# controller.net
KiCad netlist of a schematic drawn in EAGLE
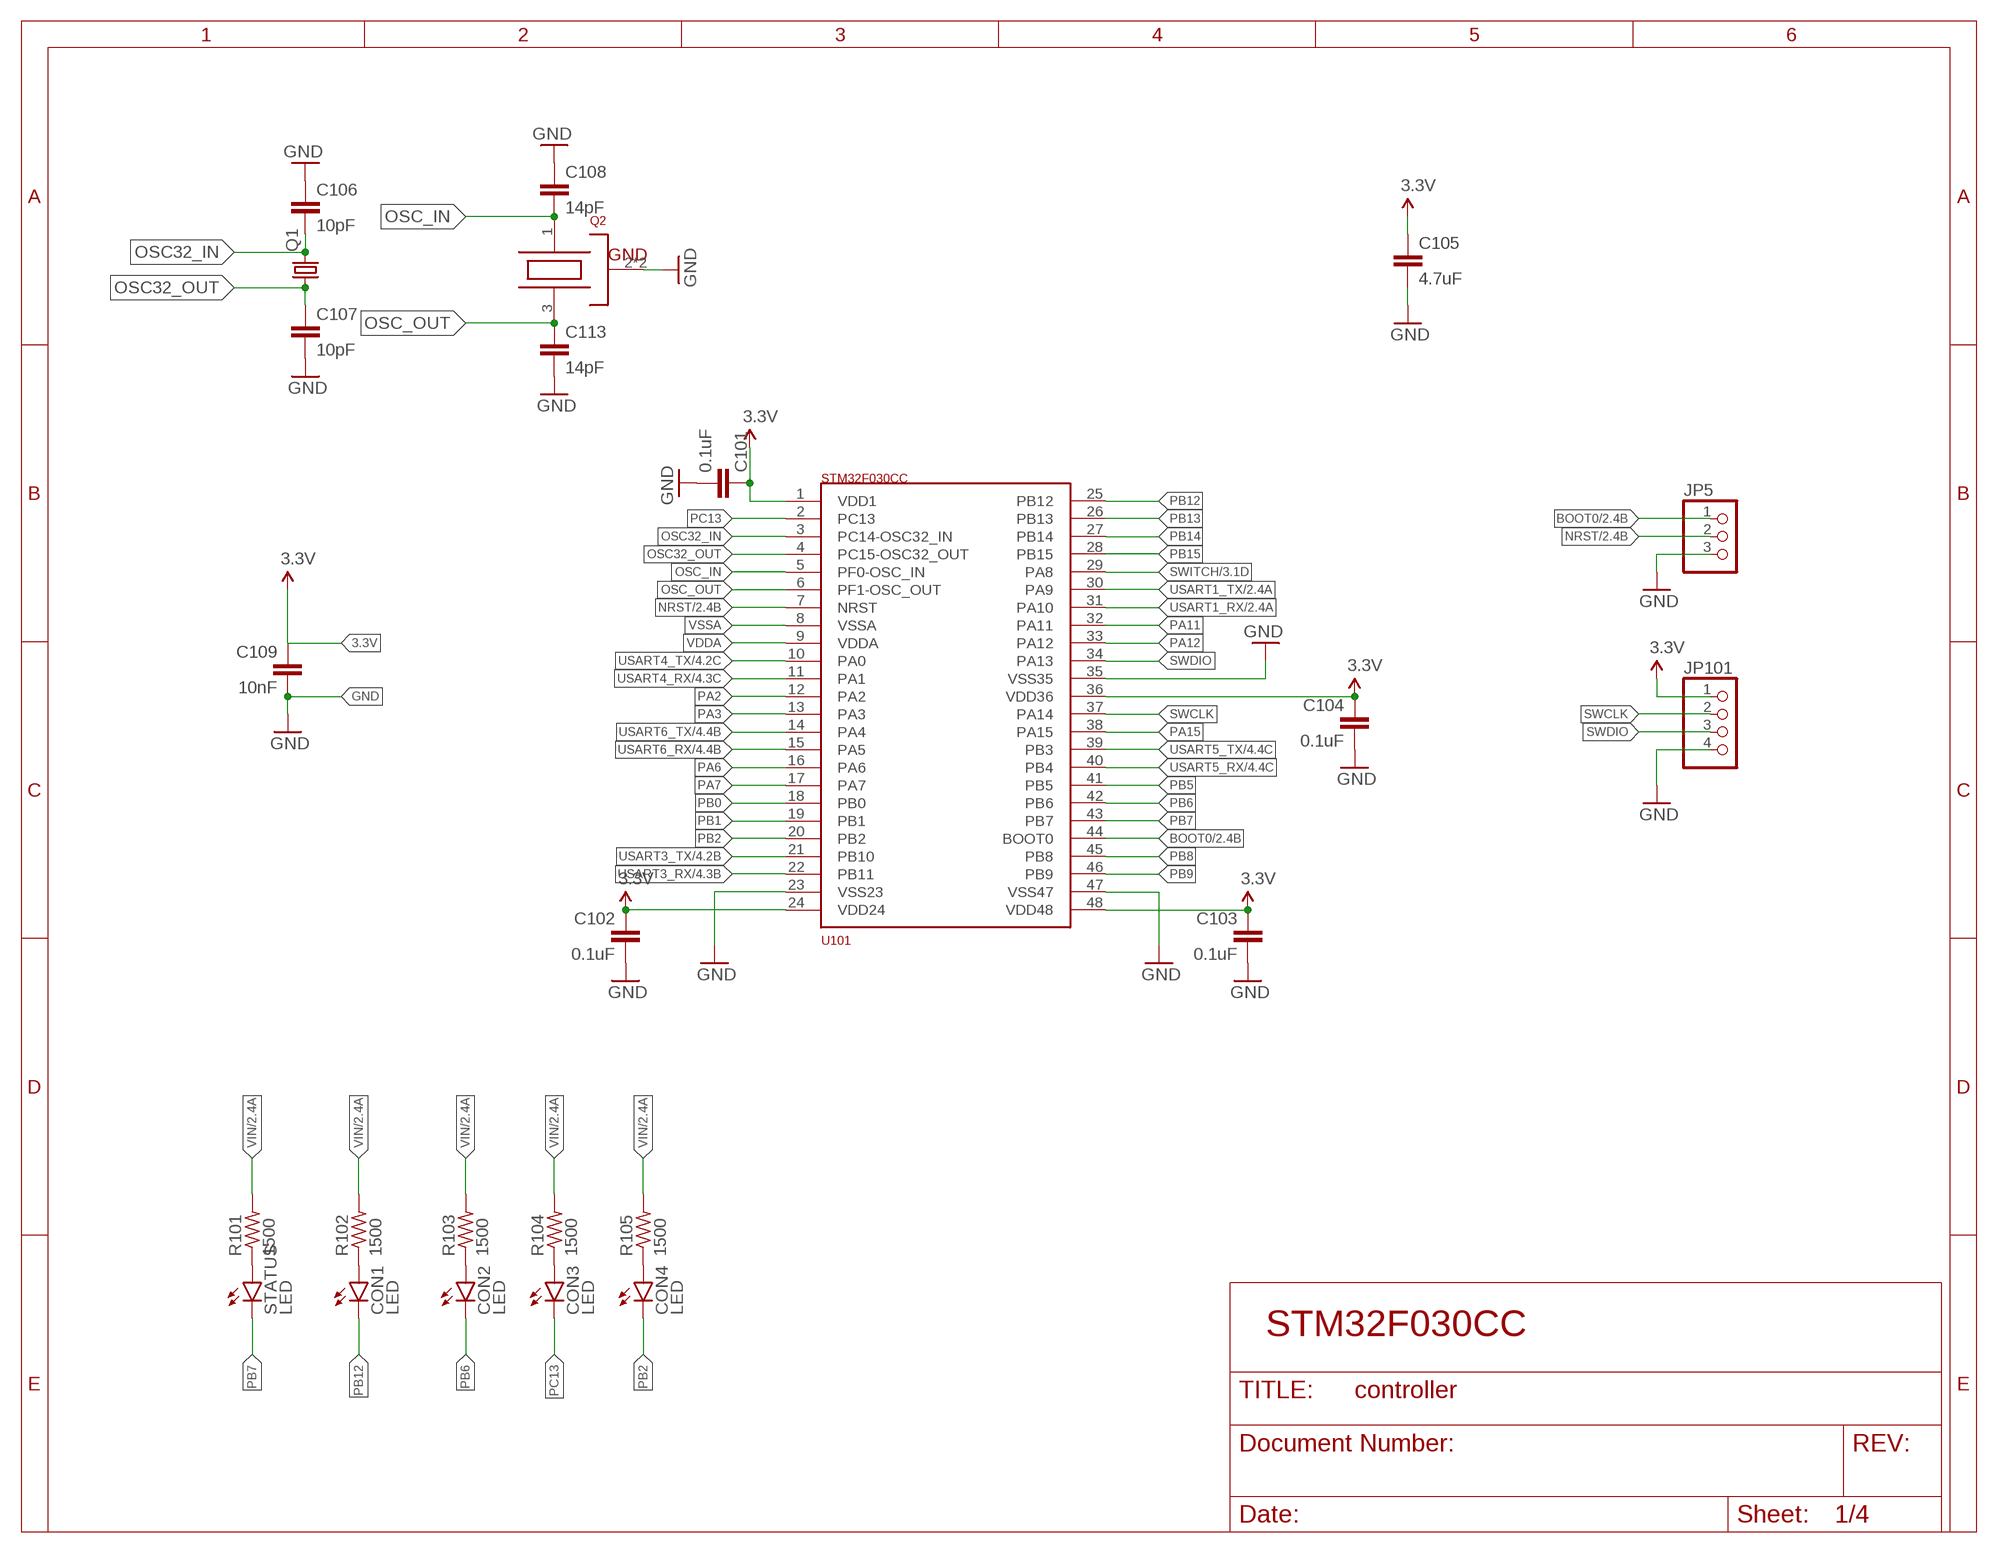
[diagram p0: schematic, sheet 1]
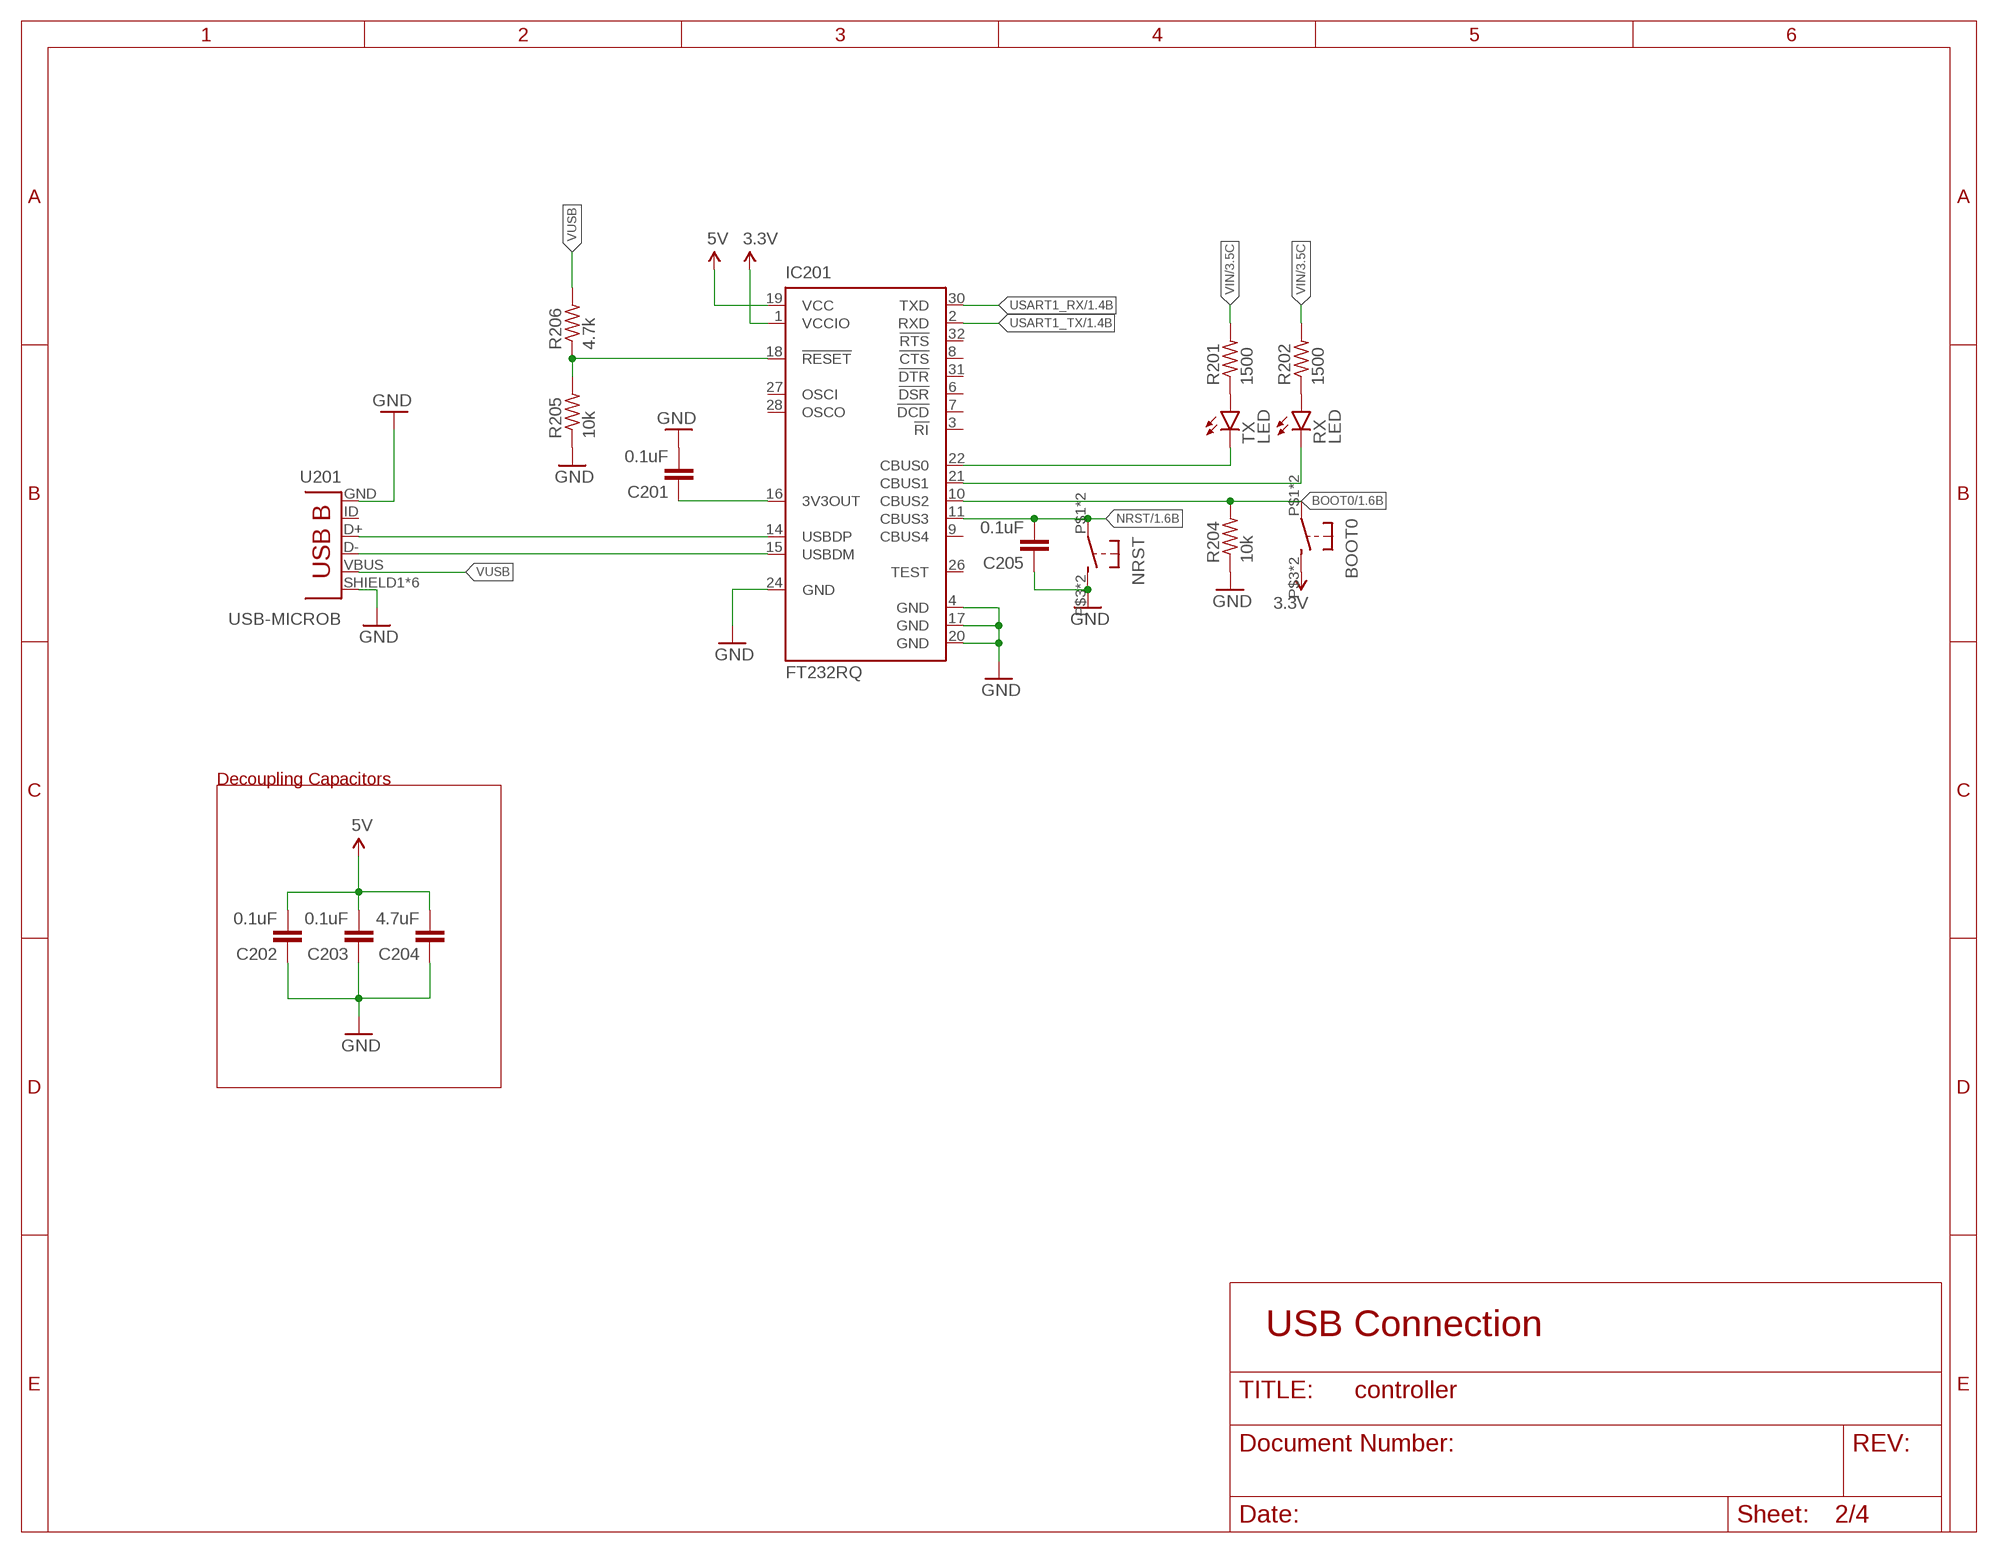
[diagram p1: schematic, sheet 2]
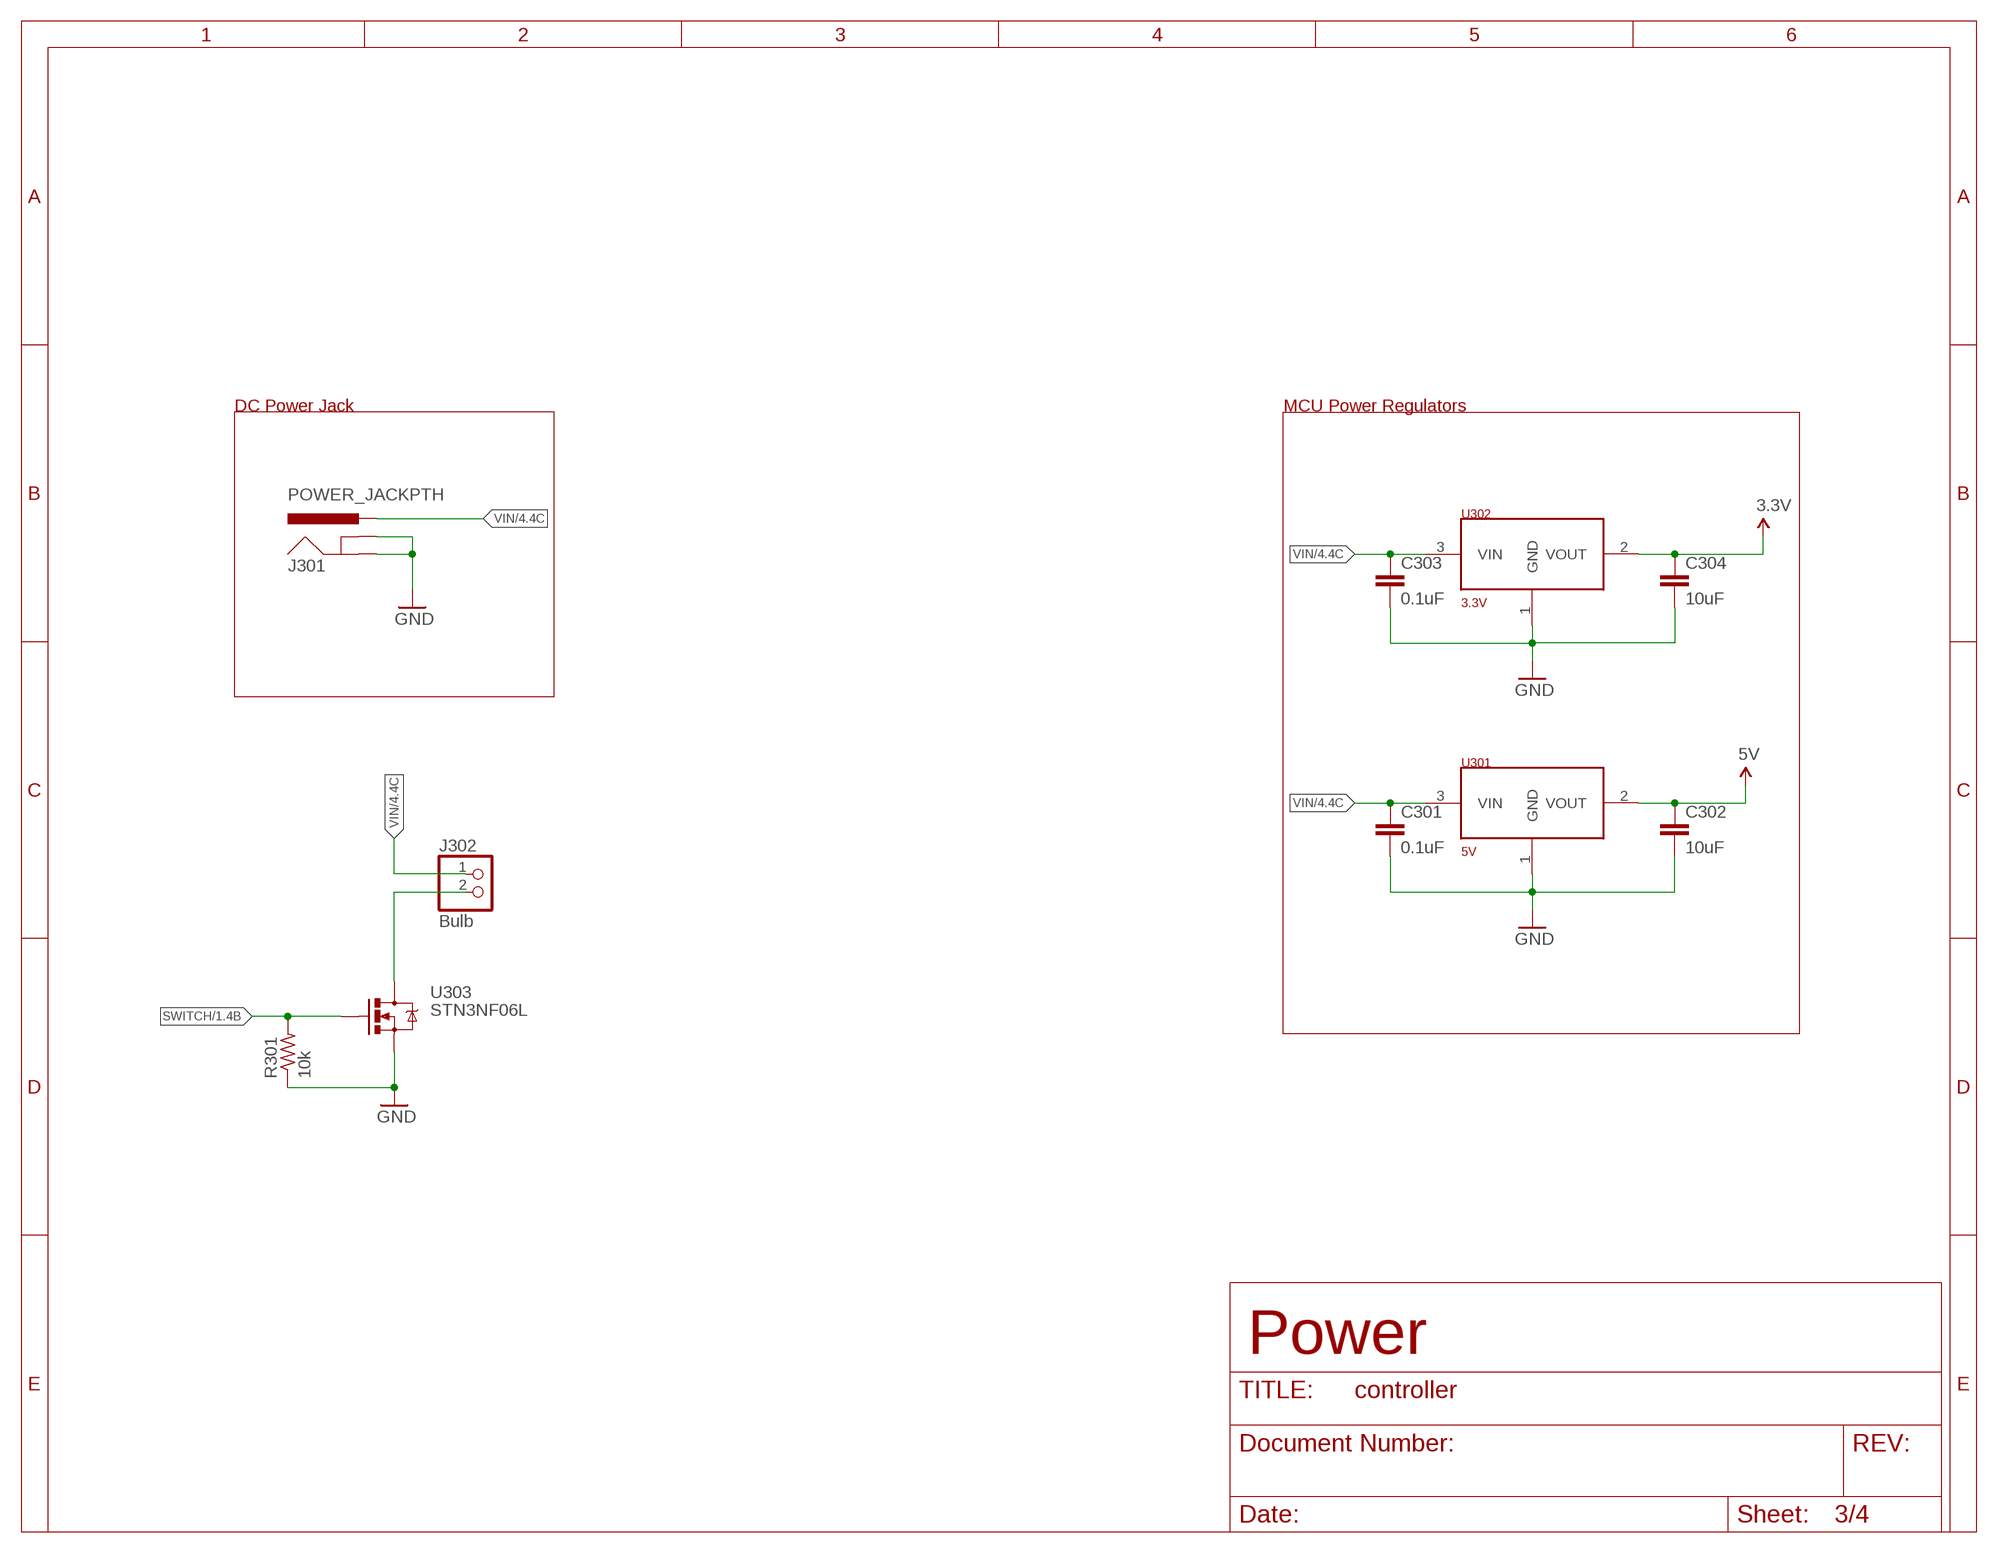
[diagram p2: schematic, sheet 3]
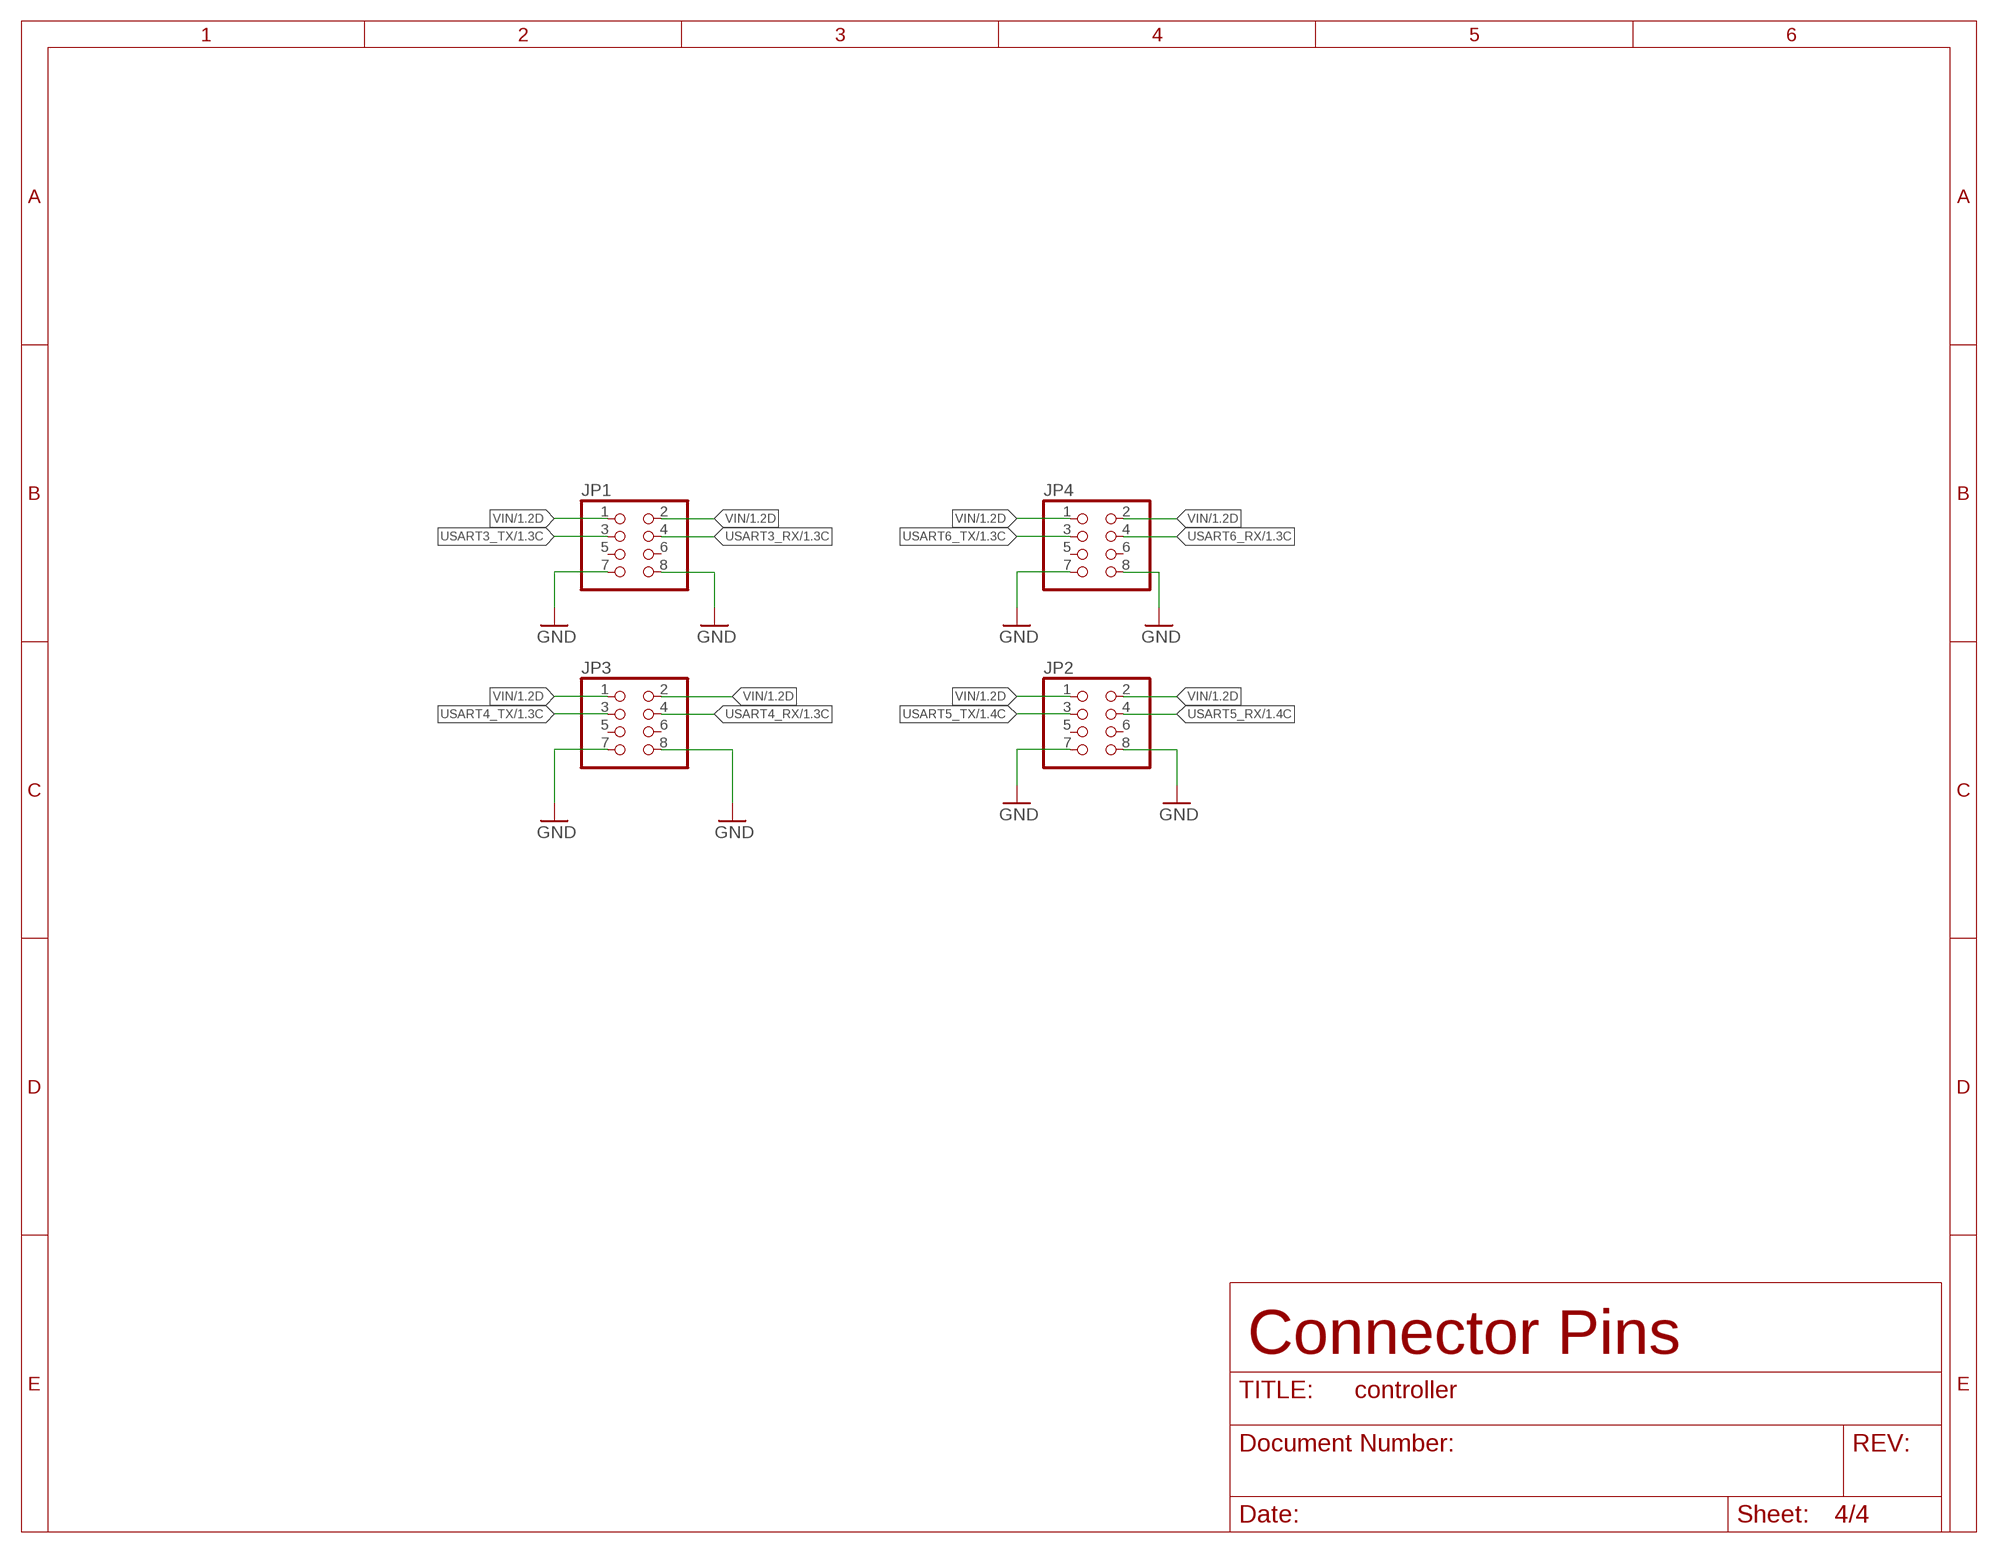
[diagram p3: schematic, sheet 4]

(export (version "E")
  (design (tool "Eeschema 10.0.6"))
  (components
    (comp (ref "JP1")
      (value "PINHD-2X4")
      (footprint "eagle-import:2X04")
      (libsource (lib "eagle-import") (part "PINHD-2X4"))
    )
    (comp (ref "JP2")
      (value "PINHD-2X4")
      (footprint "eagle-import:2X04")
      (libsource (lib "eagle-import") (part "PINHD-2X4"))
    )
    (comp (ref "JP3")
      (value "PINHD-2X4")
      (footprint "eagle-import:2X04")
      (libsource (lib "eagle-import") (part "PINHD-2X4"))
    )
    (comp (ref "JP4")
      (value "PINHD-2X4")
      (footprint "eagle-import:2X04")
      (libsource (lib "eagle-import") (part "PINHD-2X4"))
    )
    (comp (ref "C101")
      (value "0.1uF")
      (footprint "eagle-import:0603-CAP")
      (libsource (lib "eagle-import") (part "C0603"))
    )
    (comp (ref "C102")
      (value "0.1uF")
      (footprint "eagle-import:0603-CAP")
      (libsource (lib "eagle-import") (part "C0603"))
    )
    (comp (ref "C103")
      (value "0.1uF")
      (footprint "eagle-import:0603-CAP")
      (libsource (lib "eagle-import") (part "C0603"))
    )
    (comp (ref "C104")
      (value "0.1uF")
      (footprint "eagle-import:0603-CAP")
      (libsource (lib "eagle-import") (part "C0603"))
    )
    (comp (ref "C105")
      (value "4.7uF")
      (footprint "eagle-import:0603-CAP")
      (libsource (lib "eagle-import") (part "C0603"))
    )
    (comp (ref "C106")
      (value "10pF")
      (footprint "eagle-import:0603-CAP")
      (libsource (lib "eagle-import") (part "C0603"))
    )
    (comp (ref "C107")
      (value "10pF")
      (footprint "eagle-import:0603-CAP")
      (libsource (lib "eagle-import") (part "C0603"))
    )
    (comp (ref "C108")
      (value "14pF")
      (footprint "eagle-import:0603-CAP")
      (libsource (lib "eagle-import") (part "C0603"))
    )
    (comp (ref "C109")
      (value "10nF")
      (footprint "eagle-import:0603-CAP")
      (libsource (lib "eagle-import") (part "C0603"))
    )
    (comp (ref "C113")
      (value "14pF")
      (footprint "eagle-import:0603-CAP")
      (libsource (lib "eagle-import") (part "C0603"))
    )
    (comp (ref "CON1")
      (value "LED")
      (footprint "eagle-import:LED-0603")
      (libsource (lib "eagle-import") (part "LED"))
    )
    (comp (ref "CON2")
      (value "LED")
      (footprint "eagle-import:LED-0603")
      (libsource (lib "eagle-import") (part "LED"))
    )
    (comp (ref "CON3")
      (value "LED")
      (footprint "eagle-import:LED-0603")
      (libsource (lib "eagle-import") (part "LED"))
    )
    (comp (ref "CON4")
      (value "LED")
      (footprint "eagle-import:LED-0603")
      (libsource (lib "eagle-import") (part "LED"))
    )
    (comp (ref "JP5")
      (value "PINHD-1X3")
      (footprint "eagle-import:1X03")
      (libsource (lib "eagle-import") (part "PINHD-1X3"))
    )
    (comp (ref "JP101")
      (value "PINHD-1X4")
      (footprint "eagle-import:1X04")
      (libsource (lib "eagle-import") (part "PINHD-1X4"))
    )
    (comp (ref "Q1")
      (value "CRYSTALFC1610AN")
      (footprint "eagle-import:FC1610AN")
      (libsource (lib "eagle-import") (part "CRYSTALFC1610AN"))
    )
    (comp (ref "Q2")
      (value "OSCILLATOR")
      (footprint "eagle-import:OSC3.2X2.5")
      (libsource (lib "eagle-import") (part "OSCILLATOR"))
    )
    (comp (ref "R101")
      (value "1500")
      (footprint "eagle-import:R0603")
      (libsource (lib "eagle-import") (part "R0603R0603"))
    )
    (comp (ref "R102")
      (value "1500")
      (footprint "eagle-import:R0603")
      (libsource (lib "eagle-import") (part "R0603R0603"))
    )
    (comp (ref "R103")
      (value "1500")
      (footprint "eagle-import:R0603")
      (libsource (lib "eagle-import") (part "R0603R0603"))
    )
    (comp (ref "R104")
      (value "1500")
      (footprint "eagle-import:R0603")
      (libsource (lib "eagle-import") (part "R0603R0603"))
    )
    (comp (ref "R105")
      (value "1500")
      (footprint "eagle-import:R0603")
      (libsource (lib "eagle-import") (part "R0603R0603"))
    )
    (comp (ref "STATUS")
      (value "LED")
      (footprint "eagle-import:LED-0603")
      (libsource (lib "eagle-import") (part "LED"))
    )
    (comp (ref "U101")
      (value "STM32F030CC")
      (footprint "eagle-import:STM32F030CC")
      (libsource (lib "eagle-import") (part "STM32F030CC"))
    )
    (comp (ref "BOOT0")
      (value "BUTTON_MOMENTARY4P")
      (footprint "eagle-import:BUTTON_MOMENTARY_KMR211G")
      (libsource (lib "eagle-import") (part "BUTTON_MOMENTARY4P"))
    )
    (comp (ref "C201")
      (value "0.1uF")
      (footprint "eagle-import:0603-CAP")
      (libsource (lib "eagle-import") (part "C0603"))
    )
    (comp (ref "C202")
      (value "0.1uF")
      (footprint "eagle-import:0603-CAP")
      (libsource (lib "eagle-import") (part "C0603"))
    )
    (comp (ref "C203")
      (value "0.1uF")
      (footprint "eagle-import:0603-CAP")
      (libsource (lib "eagle-import") (part "C0603"))
    )
    (comp (ref "C204")
      (value "4.7uF")
      (footprint "eagle-import:0603-CAP")
      (libsource (lib "eagle-import") (part "C0603"))
    )
    (comp (ref "C205")
      (value "0.1uF")
      (footprint "eagle-import:0603-CAP")
      (libsource (lib "eagle-import") (part "C0603"))
    )
    (comp (ref "IC201")
      (value "FT232RQ")
      (footprint "eagle-import:QFN32")
      (libsource (lib "eagle-import") (part "FT232RQ"))
    )
    (comp (ref "NRST")
      (value "BUTTON_MOMENTARY4P")
      (footprint "eagle-import:BUTTON_MOMENTARY_KMR211G")
      (libsource (lib "eagle-import") (part "BUTTON_MOMENTARY4P"))
    )
    (comp (ref "R201")
      (value "1500")
      (footprint "eagle-import:R0603")
      (libsource (lib "eagle-import") (part "R0603R0603"))
    )
    (comp (ref "R202")
      (value "1500")
      (footprint "eagle-import:R0603")
      (libsource (lib "eagle-import") (part "R0603R0603"))
    )
    (comp (ref "R204")
      (value "10k")
      (footprint "eagle-import:R0603")
      (libsource (lib "eagle-import") (part "R0603R0603"))
    )
    (comp (ref "R205")
      (value "10k")
      (footprint "eagle-import:R0603")
      (libsource (lib "eagle-import") (part "R0603R0603"))
    )
    (comp (ref "R206")
      (value "4.7k")
      (footprint "eagle-import:R0603")
      (libsource (lib "eagle-import") (part "R0603R0603"))
    )
    (comp (ref "RX")
      (value "LED")
      (footprint "eagle-import:LED-0603")
      (libsource (lib "eagle-import") (part "LED"))
    )
    (comp (ref "TX")
      (value "LED")
      (footprint "eagle-import:LED-0603")
      (libsource (lib "eagle-import") (part "LED"))
    )
    (comp (ref "U201")
      (value "USB-MICROB")
      (footprint "eagle-import:USB-B-MICRO-SMD")
      (libsource (lib "eagle-import") (part "USB-MICROB"))
    )
    (comp (ref "C301")
      (value "0.1uF")
      (footprint "eagle-import:0603-CAP")
      (libsource (lib "eagle-import") (part "C0603"))
    )
    (comp (ref "C302")
      (value "10uF")
      (footprint "eagle-import:0603-CAP")
      (libsource (lib "eagle-import") (part "C0603"))
    )
    (comp (ref "C303")
      (value "0.1uF")
      (footprint "eagle-import:0603-CAP")
      (libsource (lib "eagle-import") (part "C0603"))
    )
    (comp (ref "C304")
      (value "10uF")
      (footprint "eagle-import:0603-CAP")
      (libsource (lib "eagle-import") (part "C0603"))
    )
    (comp (ref "J301")
      (value "POWER_JACKPTH")
      (footprint "eagle-import:POWER_JACK_PTH")
      (libsource (lib "eagle-import") (part "POWER_JACKPTH"))
    )
    (comp (ref "J302")
      (value "Bulb")
      (footprint "eagle-import:1X02")
      (libsource (lib "eagle-import") (part "PINHD-1X2"))
    )
    (comp (ref "R301")
      (value "10k")
      (footprint "eagle-import:R0603")
      (libsource (lib "eagle-import") (part "R0603R0603"))
    )
    (comp (ref "U301")
      (value "5V")
      (footprint "eagle-import:SOT223")
      (libsource (lib "eagle-import") (part "LD1117"))
    )
    (comp (ref "U302")
      (value "3.3V")
      (footprint "eagle-import:SOT223")
      (libsource (lib "eagle-import") (part "LD1117"))
    )
    (comp (ref "U303")
      (value "STN3NF06L")
      (footprint "eagle-import:SOT223")
      (libsource (lib "eagle-import") (part "STN3NF06L"))
    )
  )
  (nets
    (net (code "1") (name "3.3V") (class "Default")
      (node (ref "BOOT0") (pin "P$3") (pinfunction "S_P$3") (pintype "passive"))
      (node (ref "BOOT0") (pin "P$4") (pinfunction "S_P$4") (pintype "passive"))
      (node (ref "C101") (pin "1") (pinfunction "1_1") (pintype "passive"))
      (node (ref "C102") (pin "1") (pinfunction "1_1") (pintype "passive"))
      (node (ref "C103") (pin "1") (pinfunction "1_1") (pintype "passive"))
      (node (ref "C104") (pin "1") (pinfunction "1_1") (pintype "passive"))
      (node (ref "C105") (pin "1") (pinfunction "1_1") (pintype "passive"))
      (node (ref "C109") (pin "1") (pinfunction "1_1") (pintype "passive"))
      (node (ref "C304") (pin "1") (pinfunction "1_1") (pintype "passive"))
      (node (ref "IC201") (pin "1") (pinfunction "VCCIO_1") (pintype "power_in"))
      (node (ref "JP101") (pin "1") (pinfunction "1_1") (pintype "passive"))
      (node (ref "U101") (pin "1") (pinfunction "VDD1_1") (pintype "bidirectional"))
      (node (ref "U101") (pin "24") (pinfunction "VDD24_24") (pintype "bidirectional"))
      (node (ref "U101") (pin "36") (pinfunction "VDD36_36") (pintype "bidirectional"))
      (node (ref "U101") (pin "48") (pinfunction "VDD48_48") (pintype "bidirectional"))
      (node (ref "U302") (pin "2") (pinfunction "VOUT_2") (pintype "bidirectional"))
    )
    (net (code "2") (name "5V") (class "Default")
      (node (ref "C202") (pin "2") (pinfunction "2_2") (pintype "passive"))
      (node (ref "C203") (pin "2") (pinfunction "2_2") (pintype "passive"))
      (node (ref "C204") (pin "2") (pinfunction "2_2") (pintype "passive"))
      (node (ref "C302") (pin "1") (pinfunction "1_1") (pintype "passive"))
      (node (ref "IC201") (pin "19") (pinfunction "VCC_19") (pintype "power_in"))
      (node (ref "U301") (pin "2") (pinfunction "VOUT_2") (pintype "bidirectional"))
    )
    (net (code "3") (name "BOOT0") (class "Default")
      (node (ref "BOOT0") (pin "P$1") (pinfunction "P_P$1") (pintype "passive"))
      (node (ref "BOOT0") (pin "P$2") (pinfunction "P_P$2") (pintype "passive"))
      (node (ref "IC201") (pin "10") (pinfunction "CBUS2_10") (pintype "bidirectional"))
      (node (ref "JP5") (pin "1") (pinfunction "1_1") (pintype "passive"))
      (node (ref "R204") (pin "2") (pinfunction "2_2") (pintype "passive"))
      (node (ref "U101") (pin "44") (pinfunction "BOOT0_44") (pintype "bidirectional"))
    )
    (net (code "4") (name "GND") (class "Default")
      (node (ref "C101") (pin "2") (pinfunction "2_2") (pintype "passive"))
      (node (ref "C102") (pin "2") (pinfunction "2_2") (pintype "passive"))
      (node (ref "C103") (pin "2") (pinfunction "2_2") (pintype "passive"))
      (node (ref "C104") (pin "2") (pinfunction "2_2") (pintype "passive"))
      (node (ref "C105") (pin "2") (pinfunction "2_2") (pintype "passive"))
      (node (ref "C106") (pin "1") (pinfunction "1_1") (pintype "passive"))
      (node (ref "C107") (pin "2") (pinfunction "2_2") (pintype "passive"))
      (node (ref "C108") (pin "1") (pinfunction "1_1") (pintype "passive"))
      (node (ref "C109") (pin "2") (pinfunction "2_2") (pintype "passive"))
      (node (ref "C113") (pin "2") (pinfunction "2_2") (pintype "passive"))
      (node (ref "C201") (pin "2") (pinfunction "2_2") (pintype "passive"))
      (node (ref "C202") (pin "1") (pinfunction "1_1") (pintype "passive"))
      (node (ref "C203") (pin "1") (pinfunction "1_1") (pintype "passive"))
      (node (ref "C204") (pin "1") (pinfunction "1_1") (pintype "passive"))
      (node (ref "C205") (pin "1") (pinfunction "1_1") (pintype "passive"))
      (node (ref "C301") (pin "2") (pinfunction "2_2") (pintype "passive"))
      (node (ref "C302") (pin "2") (pinfunction "2_2") (pintype "passive"))
      (node (ref "C303") (pin "2") (pinfunction "2_2") (pintype "passive"))
      (node (ref "C304") (pin "2") (pinfunction "2_2") (pintype "passive"))
      (node (ref "IC201") (pin "17") (pinfunction "GND_17") (pintype "power_in"))
      (node (ref "IC201") (pin "20") (pinfunction "GND_20") (pintype "power_in"))
      (node (ref "IC201") (pin "24") (pinfunction "GND_24") (pintype "power_in"))
      (node (ref "IC201") (pin "4") (pinfunction "GND_4") (pintype "power_in"))
      (node (ref "J301") (pin "GND") (pinfunction "GND_GND") (pintype "bidirectional"))
      (node (ref "J301") (pin "GNDBREAK") (pinfunction "GNDBREAK_GNDBREAK") (pintype "bidirectional"))
      (node (ref "JP1") (pin "7") (pinfunction "7_7") (pintype "passive"))
      (node (ref "JP1") (pin "8") (pinfunction "8_8") (pintype "passive"))
      (node (ref "JP101") (pin "4") (pinfunction "4_4") (pintype "passive"))
      (node (ref "JP2") (pin "7") (pinfunction "7_7") (pintype "passive"))
      (node (ref "JP2") (pin "8") (pinfunction "8_8") (pintype "passive"))
      (node (ref "JP3") (pin "7") (pinfunction "7_7") (pintype "passive"))
      (node (ref "JP3") (pin "8") (pinfunction "8_8") (pintype "passive"))
      (node (ref "JP4") (pin "7") (pinfunction "7_7") (pintype "passive"))
      (node (ref "JP4") (pin "8") (pinfunction "8_8") (pintype "passive"))
      (node (ref "JP5") (pin "3") (pinfunction "3_3") (pintype "passive"))
      (node (ref "NRST") (pin "P$3") (pinfunction "S_P$3") (pintype "passive"))
      (node (ref "NRST") (pin "P$4") (pinfunction "S_P$4") (pintype "passive"))
      (node (ref "Q2") (pin "2") (pinfunction "GND_2") (pintype "power_in"))
      (node (ref "Q2") (pin "4") (pinfunction "GND_4") (pintype "power_in"))
      (node (ref "R204") (pin "1") (pinfunction "1_1") (pintype "passive"))
      (node (ref "R205") (pin "1") (pinfunction "1_1") (pintype "passive"))
      (node (ref "R301") (pin "1") (pinfunction "1_1") (pintype "passive"))
      (node (ref "U101") (pin "23") (pinfunction "VSS23_23") (pintype "bidirectional"))
      (node (ref "U101") (pin "35") (pinfunction "VSS35_35") (pintype "bidirectional"))
      (node (ref "U101") (pin "47") (pinfunction "VSS47_47") (pintype "bidirectional"))
      (node (ref "U201") (pin "GND") (pinfunction "GND_GND") (pintype "bidirectional"))
      (node (ref "U201") (pin "SHIELD1") (pinfunction "SHIELD_SHIELD1") (pintype "bidirectional"))
      (node (ref "U201") (pin "SHIELD2") (pinfunction "SHIELD_SHIELD2") (pintype "bidirectional"))
      (node (ref "U201") (pin "SHIELD3") (pinfunction "SHIELD_SHIELD3") (pintype "bidirectional"))
      (node (ref "U201") (pin "SHIELD4") (pinfunction "SHIELD_SHIELD4") (pintype "bidirectional"))
      (node (ref "U201") (pin "SHIELD5") (pinfunction "SHIELD_SHIELD5") (pintype "bidirectional"))
      (node (ref "U201") (pin "SHIELD6") (pinfunction "SHIELD_SHIELD6") (pintype "bidirectional"))
      (node (ref "U301") (pin "1") (pinfunction "GND_1") (pintype "bidirectional"))
      (node (ref "U302") (pin "1") (pinfunction "GND_1") (pintype "bidirectional"))
      (node (ref "U303") (pin "3") (pinfunction "S_3") (pintype "passive"))
    )
    (net (code "5") (name "NRST") (class "Default")
      (node (ref "C205") (pin "2") (pinfunction "2_2") (pintype "passive"))
      (node (ref "IC201") (pin "11") (pinfunction "CBUS3_11") (pintype "bidirectional"))
      (node (ref "JP5") (pin "2") (pinfunction "2_2") (pintype "passive"))
      (node (ref "NRST") (pin "P$1") (pinfunction "P_P$1") (pintype "passive"))
      (node (ref "NRST") (pin "P$2") (pinfunction "P_P$2") (pintype "passive"))
      (node (ref "U101") (pin "7") (pinfunction "NRST_7") (pintype "bidirectional"))
    )
    (net (code "6") (name "Net-(CON1-PadA)") (class "Default")
      (node (ref "CON1") (pin "A") (pinfunction "A_A") (pintype "passive"))
      (node (ref "R102") (pin "1") (pinfunction "1_1") (pintype "passive"))
    )
    (net (code "7") (name "Net-(CON2-PadA)") (class "Default")
      (node (ref "CON2") (pin "A") (pinfunction "A_A") (pintype "passive"))
      (node (ref "R103") (pin "1") (pinfunction "1_1") (pintype "passive"))
    )
    (net (code "8") (name "Net-(CON3-PadA)") (class "Default")
      (node (ref "CON3") (pin "A") (pinfunction "A_A") (pintype "passive"))
      (node (ref "R104") (pin "1") (pinfunction "1_1") (pintype "passive"))
    )
    (net (code "9") (name "Net-(CON4-PadA)") (class "Default")
      (node (ref "CON4") (pin "A") (pinfunction "A_A") (pintype "passive"))
      (node (ref "R105") (pin "1") (pinfunction "1_1") (pintype "passive"))
    )
    (net (code "10") (name "Net-(IC201-3V3OUT)") (class "Default")
      (node (ref "C201") (pin "1") (pinfunction "1_1") (pintype "passive"))
      (node (ref "IC201") (pin "16") (pinfunction "3V3OUT_16") (pintype "output"))
    )
    (net (code "11") (name "Net-(IC201-CBUS0)") (class "Default")
      (node (ref "IC201") (pin "22") (pinfunction "CBUS0_22") (pintype "bidirectional"))
      (node (ref "TX") (pin "C") (pinfunction "C_C") (pintype "passive"))
    )
    (net (code "12") (name "Net-(IC201-CBUS1)") (class "Default")
      (node (ref "IC201") (pin "21") (pinfunction "CBUS1_21") (pintype "bidirectional"))
      (node (ref "RX") (pin "C") (pinfunction "C_C") (pintype "passive"))
    )
    (net (code "13") (name "Net-(IC201-USBDM)") (class "Default")
      (node (ref "IC201") (pin "15") (pinfunction "USBDM_15") (pintype "bidirectional"))
      (node (ref "U201") (pin "D-") (pinfunction "D-_D-") (pintype "bidirectional"))
    )
    (net (code "14") (name "Net-(IC201-USBDP)") (class "Default")
      (node (ref "IC201") (pin "14") (pinfunction "USBDP_14") (pintype "bidirectional"))
      (node (ref "U201") (pin "D+") (pinfunction "D+_D+") (pintype "bidirectional"))
    )
    (net (code "15") (name "Net-(IC201-~{RESET})") (class "Default")
      (node (ref "IC201") (pin "18") (pinfunction "~{RESET}_18") (pintype "input"))
      (node (ref "R205") (pin "2") (pinfunction "2_2") (pintype "passive"))
      (node (ref "R206") (pin "1") (pinfunction "1_1") (pintype "passive"))
    )
    (net (code "16") (name "Net-(J302-Pad2)") (class "Default")
      (node (ref "J302") (pin "2") (pinfunction "2_2") (pintype "passive"))
      (node (ref "U303") (pin "2") (pinfunction "D_2") (pintype "passive"))
      (node (ref "U303") (pin "4") (pinfunction "D_4") (pintype "passive"))
    )
    (net (code "17") (name "Net-(R101-Pad1)") (class "Default")
      (node (ref "R101") (pin "1") (pinfunction "1_1") (pintype "passive"))
      (node (ref "STATUS") (pin "A") (pinfunction "A_A") (pintype "passive"))
    )
    (net (code "18") (name "Net-(R201-Pad1)") (class "Default")
      (node (ref "R201") (pin "1") (pinfunction "1_1") (pintype "passive"))
      (node (ref "TX") (pin "A") (pinfunction "A_A") (pintype "passive"))
    )
    (net (code "19") (name "Net-(R202-Pad1)") (class "Default")
      (node (ref "R202") (pin "1") (pinfunction "1_1") (pintype "passive"))
      (node (ref "RX") (pin "A") (pinfunction "A_A") (pintype "passive"))
    )
    (net (code "20") (name "OSC32_IN") (class "Default")
      (node (ref "C106") (pin "2") (pinfunction "2_2") (pintype "passive"))
      (node (ref "Q1") (pin "2") (pinfunction "2_2") (pintype "passive"))
      (node (ref "U101") (pin "3") (pinfunction "PC14-OSC32_IN_3") (pintype "bidirectional"))
    )
    (net (code "21") (name "OSC32_OUT") (class "Default")
      (node (ref "C107") (pin "1") (pinfunction "1_1") (pintype "passive"))
      (node (ref "Q1") (pin "1") (pinfunction "1_1") (pintype "passive"))
      (node (ref "U101") (pin "4") (pinfunction "PC15-OSC32_OUT_4") (pintype "bidirectional"))
    )
    (net (code "22") (name "OSC_IN") (class "Default")
      (node (ref "C108") (pin "2") (pinfunction "2_2") (pintype "passive"))
      (node (ref "Q2") (pin "1") (pinfunction "OSC1_1") (pintype "bidirectional"))
      (node (ref "U101") (pin "5") (pinfunction "PF0-OSC_IN_5") (pintype "bidirectional"))
    )
    (net (code "23") (name "OSC_OUT") (class "Default")
      (node (ref "C113") (pin "1") (pinfunction "1_1") (pintype "passive"))
      (node (ref "Q2") (pin "3") (pinfunction "OSC2_3") (pintype "bidirectional"))
      (node (ref "U101") (pin "6") (pinfunction "PF1-OSC_OUT_6") (pintype "bidirectional"))
    )
    (net (code "24") (name "PA2") (class "Default")
      (node (ref "U101") (pin "12") (pinfunction "PA2_12") (pintype "bidirectional"))
    )
    (net (code "25") (name "PA3") (class "Default")
      (node (ref "U101") (pin "13") (pinfunction "PA3_13") (pintype "bidirectional"))
    )
    (net (code "26") (name "PA6") (class "Default")
      (node (ref "U101") (pin "16") (pinfunction "PA6_16") (pintype "bidirectional"))
    )
    (net (code "27") (name "PA7") (class "Default")
      (node (ref "U101") (pin "17") (pinfunction "PA7_17") (pintype "bidirectional"))
    )
    (net (code "28") (name "PA11") (class "Default")
      (node (ref "U101") (pin "32") (pinfunction "PA11_32") (pintype "bidirectional"))
    )
    (net (code "29") (name "PA12") (class "Default")
      (node (ref "U101") (pin "33") (pinfunction "PA12_33") (pintype "bidirectional"))
    )
    (net (code "30") (name "PA15") (class "Default")
      (node (ref "U101") (pin "38") (pinfunction "PA15_38") (pintype "bidirectional"))
    )
    (net (code "31") (name "PB0") (class "Default")
      (node (ref "U101") (pin "18") (pinfunction "PB0_18") (pintype "bidirectional"))
    )
    (net (code "32") (name "PB1") (class "Default")
      (node (ref "U101") (pin "19") (pinfunction "PB1_19") (pintype "bidirectional"))
    )
    (net (code "33") (name "PB2") (class "Default")
      (node (ref "CON4") (pin "C") (pinfunction "C_C") (pintype "passive"))
      (node (ref "U101") (pin "20") (pinfunction "PB2_20") (pintype "bidirectional"))
    )
    (net (code "34") (name "PB5") (class "Default")
      (node (ref "U101") (pin "41") (pinfunction "PB5_41") (pintype "bidirectional"))
    )
    (net (code "35") (name "PB6") (class "Default")
      (node (ref "CON2") (pin "C") (pinfunction "C_C") (pintype "passive"))
      (node (ref "U101") (pin "42") (pinfunction "PB6_42") (pintype "bidirectional"))
    )
    (net (code "36") (name "PB7") (class "Default")
      (node (ref "STATUS") (pin "C") (pinfunction "C_C") (pintype "passive"))
      (node (ref "U101") (pin "43") (pinfunction "PB7_43") (pintype "bidirectional"))
    )
    (net (code "37") (name "PB8") (class "Default")
      (node (ref "U101") (pin "45") (pinfunction "PB8_45") (pintype "bidirectional"))
    )
    (net (code "38") (name "PB9") (class "Default")
      (node (ref "U101") (pin "46") (pinfunction "PB9_46") (pintype "bidirectional"))
    )
    (net (code "39") (name "PB12") (class "Default")
      (node (ref "CON1") (pin "C") (pinfunction "C_C") (pintype "passive"))
      (node (ref "U101") (pin "25") (pinfunction "PB12_25") (pintype "bidirectional"))
    )
    (net (code "40") (name "PB13") (class "Default")
      (node (ref "U101") (pin "26") (pinfunction "PB13_26") (pintype "bidirectional"))
    )
    (net (code "41") (name "PB14") (class "Default")
      (node (ref "U101") (pin "27") (pinfunction "PB14_27") (pintype "bidirectional"))
    )
    (net (code "42") (name "PB15") (class "Default")
      (node (ref "U101") (pin "28") (pinfunction "PB15_28") (pintype "bidirectional"))
    )
    (net (code "43") (name "PC13") (class "Default")
      (node (ref "CON3") (pin "C") (pinfunction "C_C") (pintype "passive"))
      (node (ref "U101") (pin "2") (pinfunction "PC13_2") (pintype "bidirectional"))
    )
    (net (code "44") (name "SWCLK") (class "Default")
      (node (ref "JP101") (pin "2") (pinfunction "2_2") (pintype "passive"))
      (node (ref "U101") (pin "37") (pinfunction "PA14_37") (pintype "bidirectional"))
    )
    (net (code "45") (name "SWDIO") (class "Default")
      (node (ref "JP101") (pin "3") (pinfunction "3_3") (pintype "passive"))
      (node (ref "U101") (pin "34") (pinfunction "PA13_34") (pintype "bidirectional"))
    )
    (net (code "46") (name "SWITCH") (class "Default")
      (node (ref "R301") (pin "2") (pinfunction "2_2") (pintype "passive"))
      (node (ref "U101") (pin "29") (pinfunction "PA8_29") (pintype "bidirectional"))
      (node (ref "U303") (pin "1") (pinfunction "G_1") (pintype "passive"))
    )
    (net (code "47") (name "USART1_RX") (class "Default")
      (node (ref "IC201") (pin "30") (pinfunction "TXD_30") (pintype "output"))
      (node (ref "U101") (pin "31") (pinfunction "PA10_31") (pintype "bidirectional"))
    )
    (net (code "48") (name "USART1_TX") (class "Default")
      (node (ref "IC201") (pin "2") (pinfunction "RXD_2") (pintype "input"))
      (node (ref "U101") (pin "30") (pinfunction "PA9_30") (pintype "bidirectional"))
    )
    (net (code "49") (name "USART3_RX") (class "Default")
      (node (ref "JP1") (pin "4") (pinfunction "4_4") (pintype "passive"))
      (node (ref "U101") (pin "22") (pinfunction "PB11_22") (pintype "bidirectional"))
    )
    (net (code "50") (name "USART3_TX") (class "Default")
      (node (ref "JP1") (pin "3") (pinfunction "3_3") (pintype "passive"))
      (node (ref "U101") (pin "21") (pinfunction "PB10_21") (pintype "bidirectional"))
    )
    (net (code "51") (name "USART4_RX") (class "Default")
      (node (ref "JP3") (pin "4") (pinfunction "4_4") (pintype "passive"))
      (node (ref "U101") (pin "11") (pinfunction "PA1_11") (pintype "bidirectional"))
    )
    (net (code "52") (name "USART4_TX") (class "Default")
      (node (ref "JP3") (pin "3") (pinfunction "3_3") (pintype "passive"))
      (node (ref "U101") (pin "10") (pinfunction "PA0_10") (pintype "bidirectional"))
    )
    (net (code "53") (name "USART5_RX") (class "Default")
      (node (ref "JP2") (pin "4") (pinfunction "4_4") (pintype "passive"))
      (node (ref "U101") (pin "40") (pinfunction "PB4_40") (pintype "bidirectional"))
    )
    (net (code "54") (name "USART5_TX") (class "Default")
      (node (ref "JP2") (pin "3") (pinfunction "3_3") (pintype "passive"))
      (node (ref "U101") (pin "39") (pinfunction "PB3_39") (pintype "bidirectional"))
    )
    (net (code "55") (name "USART6_RX") (class "Default")
      (node (ref "JP4") (pin "4") (pinfunction "4_4") (pintype "passive"))
      (node (ref "U101") (pin "15") (pinfunction "PA5_15") (pintype "bidirectional"))
    )
    (net (code "56") (name "USART6_TX") (class "Default")
      (node (ref "JP4") (pin "3") (pinfunction "3_3") (pintype "passive"))
      (node (ref "U101") (pin "14") (pinfunction "PA4_14") (pintype "bidirectional"))
    )
    (net (code "57") (name "VDDA") (class "Default")
      (node (ref "U101") (pin "9") (pinfunction "VDDA_9") (pintype "bidirectional"))
    )
    (net (code "58") (name "VIN") (class "Default")
      (node (ref "C301") (pin "1") (pinfunction "1_1") (pintype "passive"))
      (node (ref "C303") (pin "1") (pinfunction "1_1") (pintype "passive"))
      (node (ref "J301") (pin "PWR") (pinfunction "PWR_PWR") (pintype "bidirectional"))
      (node (ref "J302") (pin "1") (pinfunction "1_1") (pintype "passive"))
      (node (ref "JP1") (pin "1") (pinfunction "1_1") (pintype "passive"))
      (node (ref "JP1") (pin "2") (pinfunction "2_2") (pintype "passive"))
      (node (ref "JP2") (pin "1") (pinfunction "1_1") (pintype "passive"))
      (node (ref "JP2") (pin "2") (pinfunction "2_2") (pintype "passive"))
      (node (ref "JP3") (pin "1") (pinfunction "1_1") (pintype "passive"))
      (node (ref "JP3") (pin "2") (pinfunction "2_2") (pintype "passive"))
      (node (ref "JP4") (pin "1") (pinfunction "1_1") (pintype "passive"))
      (node (ref "JP4") (pin "2") (pinfunction "2_2") (pintype "passive"))
      (node (ref "R101") (pin "2") (pinfunction "2_2") (pintype "passive"))
      (node (ref "R102") (pin "2") (pinfunction "2_2") (pintype "passive"))
      (node (ref "R103") (pin "2") (pinfunction "2_2") (pintype "passive"))
      (node (ref "R104") (pin "2") (pinfunction "2_2") (pintype "passive"))
      (node (ref "R105") (pin "2") (pinfunction "2_2") (pintype "passive"))
      (node (ref "R201") (pin "2") (pinfunction "2_2") (pintype "passive"))
      (node (ref "R202") (pin "2") (pinfunction "2_2") (pintype "passive"))
      (node (ref "U301") (pin "3") (pinfunction "VIN_3") (pintype "bidirectional"))
      (node (ref "U302") (pin "3") (pinfunction "VIN_3") (pintype "bidirectional"))
    )
    (net (code "59") (name "VSSA") (class "Default")
      (node (ref "U101") (pin "8") (pinfunction "VSSA_8") (pintype "bidirectional"))
    )
    (net (code "60") (name "VUSB") (class "Default")
      (node (ref "R206") (pin "2") (pinfunction "2_2") (pintype "passive"))
      (node (ref "U201") (pin "VBUS") (pinfunction "VBUS_VBUS") (pintype "bidirectional"))
    )
    (net (code "61") (name "unconnected-(IC201-CBUS4-Pad9)") (class "Default")
      (node (ref "IC201") (pin "9") (pinfunction "CBUS4_9") (pintype "bidirectional"))
    )
    (net (code "62") (name "unconnected-(IC201-OSCI-Pad27)") (class "Default")
      (node (ref "IC201") (pin "27") (pinfunction "OSCI_27") (pintype "input"))
    )
    (net (code "63") (name "unconnected-(IC201-OSCO-Pad28)") (class "Default")
      (node (ref "IC201") (pin "28") (pinfunction "OSCO_28") (pintype "output"))
    )
    (net (code "64") (name "unconnected-(IC201-TEST-Pad26)") (class "Default")
      (node (ref "IC201") (pin "26") (pinfunction "TEST_26") (pintype "input"))
    )
    (net (code "65") (name "unconnected-(IC201-~{CTS}-Pad8)") (class "Default")
      (node (ref "IC201") (pin "8") (pinfunction "~{CTS}_8") (pintype "input"))
    )
    (net (code "66") (name "unconnected-(IC201-~{DCD}-Pad7)") (class "Default")
      (node (ref "IC201") (pin "7") (pinfunction "~{DCD}_7") (pintype "input"))
    )
    (net (code "67") (name "unconnected-(IC201-~{DSR}-Pad6)") (class "Default")
      (node (ref "IC201") (pin "6") (pinfunction "~{DSR}_6") (pintype "input"))
    )
    (net (code "68") (name "unconnected-(IC201-~{DTR}-Pad31)") (class "Default")
      (node (ref "IC201") (pin "31") (pinfunction "~{DTR}_31") (pintype "output"))
    )
    (net (code "69") (name "unconnected-(IC201-~{RI}-Pad3)") (class "Default")
      (node (ref "IC201") (pin "3") (pinfunction "~{RI}_3") (pintype "input"))
    )
    (net (code "70") (name "unconnected-(IC201-~{RTS}-Pad32)") (class "Default")
      (node (ref "IC201") (pin "32") (pinfunction "~{RTS}_32") (pintype "output"))
    )
    (net (code "71") (name "unconnected-(JP1-Pad5)") (class "Default")
      (node (ref "JP1") (pin "5") (pinfunction "5_5") (pintype "passive"))
    )
    (net (code "72") (name "unconnected-(JP1-Pad6)") (class "Default")
      (node (ref "JP1") (pin "6") (pinfunction "6_6") (pintype "passive"))
    )
    (net (code "73") (name "unconnected-(JP2-Pad5)") (class "Default")
      (node (ref "JP2") (pin "5") (pinfunction "5_5") (pintype "passive"))
    )
    (net (code "74") (name "unconnected-(JP2-Pad6)") (class "Default")
      (node (ref "JP2") (pin "6") (pinfunction "6_6") (pintype "passive"))
    )
    (net (code "75") (name "unconnected-(JP3-Pad5)") (class "Default")
      (node (ref "JP3") (pin "5") (pinfunction "5_5") (pintype "passive"))
    )
    (net (code "76") (name "unconnected-(JP3-Pad6)") (class "Default")
      (node (ref "JP3") (pin "6") (pinfunction "6_6") (pintype "passive"))
    )
    (net (code "77") (name "unconnected-(JP4-Pad5)") (class "Default")
      (node (ref "JP4") (pin "5") (pinfunction "5_5") (pintype "passive"))
    )
    (net (code "78") (name "unconnected-(JP4-Pad6)") (class "Default")
      (node (ref "JP4") (pin "6") (pinfunction "6_6") (pintype "passive"))
    )
    (net (code "79") (name "unconnected-(U201-USBID-PadID)") (class "Default")
      (node (ref "U201") (pin "ID") (pinfunction "USBID_ID") (pintype "bidirectional"))
    )
  )
)
